# Audio_Output_Line_Out.net
KiCad netlist of a schematic drawn in Altium Designer
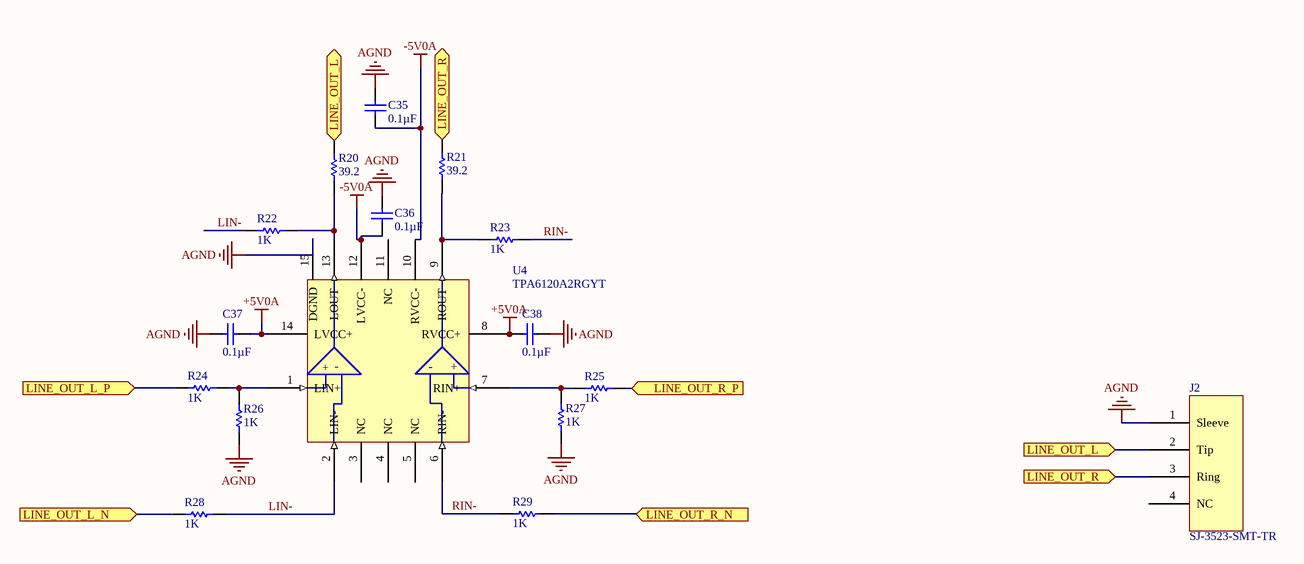
[diagram p0: Audio_Output_Line_Out.SchDoc]

(export (version "E")
  (design (tool "Eeschema 10.0.6"))
  (components
    (comp (ref "C35")
      (value "C1608X7R1H104K")
      (footprint "3-0603_L")
      (description "CAP CER 0.1UF 50V 10% X7R 0603")
      (fields
        (field (name "MANUFACTURER") "TDK Corporation")
        (field (name "TOLERANCE") "±10%")
        (field (name "CAPACITANCE") "0.1µF")
      )
      (libsource (lib "Schematic_Components") (part "C1608X7R1H104K"))
    )
    (comp (ref "C36")
      (value "C1608X7R1H104K")
      (footprint "3-0603_L")
      (description "CAP CER 0.1UF 50V 10% X7R 0603")
      (fields
        (field (name "MANUFACTURER") "TDK Corporation")
        (field (name "TOLERANCE") "±10%")
        (field (name "CAPACITANCE") "0.1µF")
      )
      (libsource (lib "Schematic_Components") (part "C1608X7R1H104K"))
    )
    (comp (ref "C37")
      (value "C1608X7R1H104K")
      (footprint "3-0603_L")
      (description "CAP CER 0.1UF 50V 10% X7R 0603")
      (fields
        (field (name "MANUFACTURER") "TDK Corporation")
        (field (name "TOLERANCE") "±10%")
        (field (name "CAPACITANCE") "0.1µF")
      )
      (libsource (lib "Schematic_Components") (part "C1608X7R1H104K"))
    )
    (comp (ref "C38")
      (value "C1608X7R1H104K")
      (footprint "3-0603_L")
      (description "CAP CER 0.1UF 50V 10% X7R 0603")
      (fields
        (field (name "MANUFACTURER") "TDK Corporation")
        (field (name "TOLERANCE") "±10%")
        (field (name "CAPACITANCE") "0.1µF")
      )
      (libsource (lib "Schematic_Components") (part "C1608X7R1H104K"))
    )
    (comp (ref "J2")
      (value "SJ-3523-SMT-TR")
      (footprint "SJ-3523-SMT-TR")
      (description "3.50mm (0.141\", 1/8\", Mini Plug) - Headphone Phone Jack Stereo Connector Solder")
      (fields
        (field (name "MANUFACTURER") "CUI Inc.")
        (field (name "MANUFACTURER PART NUMBER") "SJ-3523-SMT-TR")
        (field (name "PUBLISHER") "Altium Limited")
      )
      (libsource (lib "NIH_DE0_Nano_Daughter_Card_Library") (part "SJ-3523-SMT-TR"))
    )
    (comp (ref "R20")
      (value "ERJ-3EKF39R2V")
      (footprint "3-0603_R_L")
      (description "n RES SMD 39.2 OHM 1% 1/10W 0603")
      (fields
        (field (name "MANUFACTURER") "Panasonic Electronic Components")
        (field (name "TOLERANCE") "±1%")
        (field (name "RESISTANCE (OHMS)") "39.2")
      )
      (libsource (lib "Schematic_Components") (part "ERJ-3EKF39R2V"))
    )
    (comp (ref "R21")
      (value "ERJ-3EKF39R2V")
      (footprint "3-0603_R_L")
      (description "n RES SMD 39.2 OHM 1% 1/10W 0603")
      (fields
        (field (name "MANUFACTURER") "Panasonic Electronic Components")
        (field (name "TOLERANCE") "±1%")
        (field (name "RESISTANCE (OHMS)") "39.2")
      )
      (libsource (lib "Schematic_Components") (part "ERJ-3EKF39R2V"))
    )
    (comp (ref "R22")
      (value "ERJ-3EKF1001V")
      (footprint "3-0603_R_L")
      (description "RES 1.00K OHM 1/10W 1% 0603 SMD")
      (fields
        (field (name "MANUFACTURER") "Panasonic - ECG")
        (field (name "TOLERANCE") "±1%")
        (field (name "RESISTANCE (OHMS)") "1K")
      )
      (libsource (lib "Schematic_Components") (part "ERJ-3EKF1001V"))
    )
    (comp (ref "R23")
      (value "ERJ-3EKF1001V")
      (footprint "3-0603_R_L")
      (description "RES 1.00K OHM 1/10W 1% 0603 SMD")
      (fields
        (field (name "MANUFACTURER") "Panasonic - ECG")
        (field (name "TOLERANCE") "±1%")
        (field (name "RESISTANCE (OHMS)") "1K")
      )
      (libsource (lib "Schematic_Components") (part "ERJ-3EKF1001V"))
    )
    (comp (ref "R24")
      (value "ERJ-3EKF1001V")
      (footprint "3-0603_R_L")
      (description "RES 1.00K OHM 1/10W 1% 0603 SMD")
      (fields
        (field (name "MANUFACTURER") "Panasonic - ECG")
        (field (name "TOLERANCE") "±1%")
        (field (name "RESISTANCE (OHMS)") "1K")
      )
      (libsource (lib "Schematic_Components") (part "ERJ-3EKF1001V"))
    )
    (comp (ref "R25")
      (value "ERJ-3EKF1001V")
      (footprint "3-0603_R_L")
      (description "RES 1.00K OHM 1/10W 1% 0603 SMD")
      (fields
        (field (name "MANUFACTURER") "Panasonic - ECG")
        (field (name "TOLERANCE") "±1%")
        (field (name "RESISTANCE (OHMS)") "1K")
      )
      (libsource (lib "Schematic_Components") (part "ERJ-3EKF1001V"))
    )
    (comp (ref "R26")
      (value "ERJ-3EKF1001V")
      (footprint "3-0603_R_L")
      (description "RES 1.00K OHM 1/10W 1% 0603 SMD")
      (fields
        (field (name "MANUFACTURER") "Panasonic - ECG")
        (field (name "TOLERANCE") "±1%")
        (field (name "RESISTANCE (OHMS)") "1K")
      )
      (libsource (lib "Schematic_Components") (part "ERJ-3EKF1001V"))
    )
    (comp (ref "R27")
      (value "ERJ-3EKF1001V")
      (footprint "3-0603_R_L")
      (description "RES 1.00K OHM 1/10W 1% 0603 SMD")
      (fields
        (field (name "MANUFACTURER") "Panasonic - ECG")
        (field (name "TOLERANCE") "±1%")
        (field (name "RESISTANCE (OHMS)") "1K")
      )
      (libsource (lib "Schematic_Components") (part "ERJ-3EKF1001V"))
    )
    (comp (ref "R28")
      (value "ERJ-3EKF1001V")
      (footprint "3-0603_R_L")
      (description "RES 1.00K OHM 1/10W 1% 0603 SMD")
      (fields
        (field (name "MANUFACTURER") "Panasonic - ECG")
        (field (name "TOLERANCE") "±1%")
        (field (name "RESISTANCE (OHMS)") "1K")
      )
      (libsource (lib "Schematic_Components") (part "ERJ-3EKF1001V"))
    )
    (comp (ref "R29")
      (value "ERJ-3EKF1001V")
      (footprint "3-0603_R_L")
      (description "RES 1.00K OHM 1/10W 1% 0603 SMD")
      (fields
        (field (name "MANUFACTURER") "Panasonic - ECG")
        (field (name "TOLERANCE") "±1%")
        (field (name "RESISTANCE (OHMS)") "1K")
      )
      (libsource (lib "Schematic_Components") (part "ERJ-3EKF1001V"))
    )
    (comp (ref "U4")
      (value "TPA6120A2RGYT")
      (footprint "PQFN50P350X350X100_HS-15N")
      (description "Amplifier IC Headphones, 2-Channel (Stereo) Class AB 14-VQFN (3.5x3.5)")
      (fields
        (field (name "MANUFACTURER") "Texas Instruments")
        (field (name "MANUFACTURER PART NUMBER") "TPA6120A2RGYT")
        (field (name "PUBLISHER") "Altium Limited")
      )
      (libsource (lib "NIH_DE0_Nano_Daughter_Card_Library") (part "TPA6120A2RGYT"))
    )
  )
  (nets
    (net (code "1") (name "+5V0A") (class "Default")
      (node (ref "C37") (pin "2") (pinfunction "2_2") (pintype "passive"))
      (node (ref "C38") (pin "2") (pinfunction "2_2") (pintype "passive"))
      (node (ref "U4") (pin "14") (pinfunction "LVCC+_14") (pintype "passive"))
      (node (ref "U4") (pin "8") (pinfunction "RVCC+_8") (pintype "passive"))
    )
    (net (code "2") (name "-5V0A") (class "Default")
      (node (ref "C35") (pin "2") (pinfunction "2_2") (pintype "passive"))
      (node (ref "C36") (pin "2") (pinfunction "2_2") (pintype "passive"))
      (node (ref "U4") (pin "10") (pinfunction "RVCC-_10") (pintype "passive"))
      (node (ref "U4") (pin "12") (pinfunction "LVCC-_12") (pintype "passive"))
    )
    (net (code "3") (name "/LIN-") (class "Default")
      (node (ref "R22") (pin "1") (pinfunction "1_1") (pintype "passive"))
      (node (ref "R28") (pin "2") (pinfunction "2_2") (pintype "passive"))
      (node (ref "U4") (pin "2") (pinfunction "LIN-_2") (pintype "input"))
    )
    (net (code "4") (name "/LINE_OUT_L") (class "Default")
      (node (ref "J2") (pin "2") (pinfunction "Tip_2") (pintype "passive"))
      (node (ref "R20") (pin "1") (pinfunction "1_1") (pintype "passive"))
    )
    (net (code "5") (name "/LINE_OUT_L_N") (class "Default")
      (node (ref "R28") (pin "1") (pinfunction "1_1") (pintype "passive"))
    )
    (net (code "6") (name "/LINE_OUT_L_P") (class "Default")
      (node (ref "R24") (pin "1") (pinfunction "1_1") (pintype "passive"))
    )
    (net (code "7") (name "/LINE_OUT_R") (class "Default")
      (node (ref "J2") (pin "3") (pinfunction "Ring_3") (pintype "passive"))
      (node (ref "R21") (pin "1") (pinfunction "1_1") (pintype "passive"))
    )
    (net (code "8") (name "/LINE_OUT_R_N") (class "Default")
      (node (ref "R29") (pin "2") (pinfunction "2_2") (pintype "passive"))
    )
    (net (code "9") (name "/LINE_OUT_R_P") (class "Default")
      (node (ref "R25") (pin "2") (pinfunction "2_2") (pintype "passive"))
    )
    (net (code "10") (name "/RIN-") (class "Default")
      (node (ref "R23") (pin "1") (pinfunction "1_1") (pintype "passive"))
      (node (ref "R29") (pin "1") (pinfunction "1_1") (pintype "passive"))
      (node (ref "U4") (pin "6") (pinfunction "RIN-_6") (pintype "input"))
    )
    (net (code "11") (name "AGND") (class "Default")
      (node (ref "C35") (pin "1") (pinfunction "1_1") (pintype "passive"))
      (node (ref "C36") (pin "1") (pinfunction "1_1") (pintype "passive"))
      (node (ref "C37") (pin "1") (pinfunction "1_1") (pintype "passive"))
      (node (ref "C38") (pin "1") (pinfunction "1_1") (pintype "passive"))
      (node (ref "J2") (pin "1") (pinfunction "Sleeve_1") (pintype "passive"))
      (node (ref "R26") (pin "1") (pinfunction "1_1") (pintype "passive"))
      (node (ref "R27") (pin "1") (pinfunction "1_1") (pintype "passive"))
      (node (ref "U4") (pin "15") (pinfunction "DGND_15") (pintype "passive"))
    )
    (net (code "12") (name "Net-(U4-LIN+)") (class "Default")
      (node (ref "R24") (pin "2") (pinfunction "2_2") (pintype "passive"))
      (node (ref "R26") (pin "2") (pinfunction "2_2") (pintype "passive"))
      (node (ref "U4") (pin "1") (pinfunction "LIN+_1") (pintype "input"))
    )
    (net (code "13") (name "Net-(U4-LOUT)") (class "Default")
      (node (ref "R20") (pin "2") (pinfunction "2_2") (pintype "passive"))
      (node (ref "R22") (pin "2") (pinfunction "2_2") (pintype "passive"))
      (node (ref "U4") (pin "13") (pinfunction "LOUT_13") (pintype "output"))
    )
    (net (code "14") (name "Net-(U4-RIN+)") (class "Default")
      (node (ref "R25") (pin "1") (pinfunction "1_1") (pintype "passive"))
      (node (ref "R27") (pin "2") (pinfunction "2_2") (pintype "passive"))
      (node (ref "U4") (pin "7") (pinfunction "RIN+_7") (pintype "input"))
    )
    (net (code "15") (name "Net-(U4-ROUT)") (class "Default")
      (node (ref "R21") (pin "2") (pinfunction "2_2") (pintype "passive"))
      (node (ref "R23") (pin "2") (pinfunction "2_2") (pintype "passive"))
      (node (ref "U4") (pin "9") (pinfunction "ROUT_9") (pintype "output"))
    )
    (net (code "16") (name "unconnected-(J2-NC-Pad4)") (class "Default")
      (node (ref "J2") (pin "4") (pinfunction "NC_4") (pintype "passive"))
    )
    (net (code "17") (name "unconnected-(U4-NC-Pad3)") (class "Default")
      (node (ref "U4") (pin "3") (pinfunction "NC_3") (pintype "passive"))
    )
    (net (code "18") (name "unconnected-(U4-NC-Pad4)") (class "Default")
      (node (ref "U4") (pin "4") (pinfunction "NC_4") (pintype "passive"))
    )
    (net (code "19") (name "unconnected-(U4-NC-Pad5)") (class "Default")
      (node (ref "U4") (pin "5") (pinfunction "NC_5") (pintype "passive"))
    )
    (net (code "20") (name "unconnected-(U4-NC-Pad11)") (class "Default")
      (node (ref "U4") (pin "11") (pinfunction "NC_11") (pintype "passive"))
    )
  )
)
